# gomasuno.net
KiCad netlist of a schematic drawn in EAGLE
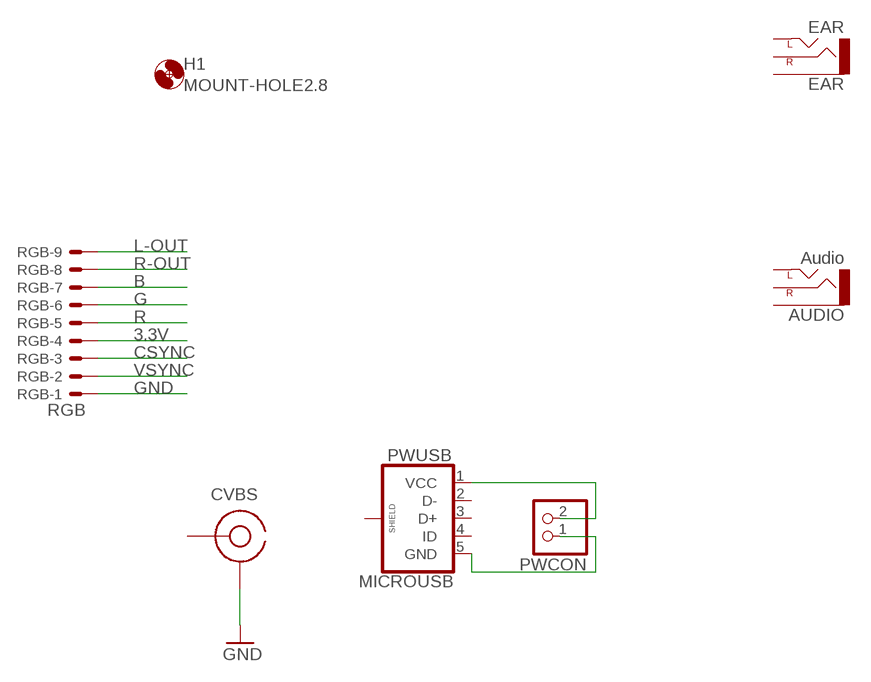
[diagram p0: schematic, sheet 1]

(export (version "E")
  (design (tool "Eeschema 10.0.6"))
  (components
    (comp (ref "AUDIO")
      (value "Audio")
      (footprint "eagle-import:AUDIO-JACK")
      (libsource (lib "eagle-import") (part "AUDIO-JACKPTH"))
    )
    (comp (ref "CVBS")
      (value "RCA")
      (footprint "eagle-import:RCA")
      (libsource (lib "eagle-import") (part "RCA"))
    )
    (comp (ref "EAR")
      (value "EAR")
      (footprint "eagle-import:AUDIO-JACK")
      (libsource (lib "eagle-import") (part "AUDIO-JACKPTH"))
    )
    (comp (ref "H1")
      (value "MOUNT-HOLE2.8")
      (footprint "eagle-import:2,8")
      (libsource (lib "eagle-import") (part "MOUNT-HOLE2.8"))
    )
    (comp (ref "PWCON")
      (value "PINHD-1X2")
      (footprint "eagle-import:1X02")
      (libsource (lib "eagle-import") (part "PINHD-1X2"))
    )
    (comp (ref "PWUSB")
      (value "MICROUSB")
      (footprint "eagle-import:MICRO_USB_1PRIMARY")
      (libsource (lib "eagle-import") (part "MICROUSB"))
    )
    (comp (ref "RGB")
      (value "RGB")
      (footprint "eagle-import:53048-09")
      (fields (field (name "MPN") "53048-0910"))
      (libsource (lib "eagle-import") (part "53?-09048"))
    )
  )
  (nets
    (net (code "1") (name "/3.3V") (class "Default")
      (node (ref "RGB") (pin "4") (pinfunction "S_4") (pintype "passive"))
    )
    (net (code "2") (name "/B") (class "Default")
      (node (ref "RGB") (pin "7") (pinfunction "S_7") (pintype "passive"))
    )
    (net (code "3") (name "/CSYNC") (class "Default")
      (node (ref "RGB") (pin "3") (pinfunction "S_3") (pintype "passive"))
    )
    (net (code "4") (name "/G") (class "Default")
      (node (ref "RGB") (pin "6") (pinfunction "S_6") (pintype "passive"))
    )
    (net (code "5") (name "/L-OUT") (class "Default")
      (node (ref "RGB") (pin "9") (pinfunction "S_9") (pintype "passive"))
    )
    (net (code "6") (name "/R") (class "Default")
      (node (ref "RGB") (pin "5") (pinfunction "S_5") (pintype "passive"))
    )
    (net (code "7") (name "/R-OUT") (class "Default")
      (node (ref "RGB") (pin "8") (pinfunction "S_8") (pintype "passive"))
    )
    (net (code "8") (name "/VSYNC") (class "Default")
      (node (ref "RGB") (pin "2") (pinfunction "S_2") (pintype "passive"))
    )
    (net (code "9") (name "GND") (class "Default")
      (node (ref "CVBS") (pin "GND") (pinfunction "GND_GND") (pintype "passive"))
      (node (ref "PWCON") (pin "1") (pinfunction "1_1") (pintype "passive"))
      (node (ref "PWUSB") (pin "5") (pinfunction "GND_5") (pintype "bidirectional"))
      (node (ref "RGB") (pin "1") (pinfunction "S_1") (pintype "passive"))
    )
    (net (code "10") (name "Net-(PWUSB-VCC)") (class "Default")
      (node (ref "PWCON") (pin "2") (pinfunction "2_2") (pintype "passive"))
      (node (ref "PWUSB") (pin "1") (pinfunction "VCC_1") (pintype "bidirectional"))
    )
    (net (code "11") (name "unconnected-(AUDIO-LEFT-PadTIP)") (class "Default")
      (node (ref "AUDIO") (pin "TIP") (pinfunction "LEFT_TIP") (pintype "bidirectional"))
    )
    (net (code "12") (name "unconnected-(AUDIO-PadSLEEVE)") (class "Default")
      (node (ref "AUDIO") (pin "SLEEVE") (pinfunction "SLEEVE_SLEEVE") (pintype "bidirectional"))
    )
    (net (code "13") (name "unconnected-(AUDIO-RIGHT-PadRING)") (class "Default")
      (node (ref "AUDIO") (pin "RING") (pinfunction "RIGHT_RING") (pintype "bidirectional"))
    )
    (net (code "14") (name "unconnected-(CVBS-PadSIG)") (class "Default")
      (node (ref "CVBS") (pin "SIG") (pinfunction "SIG_SIG") (pintype "passive"))
    )
    (net (code "15") (name "unconnected-(EAR-LEFT-PadTIP)") (class "Default")
      (node (ref "EAR") (pin "TIP") (pinfunction "LEFT_TIP") (pintype "bidirectional"))
    )
    (net (code "16") (name "unconnected-(EAR-PadSLEEVE)") (class "Default")
      (node (ref "EAR") (pin "SLEEVE") (pinfunction "SLEEVE_SLEEVE") (pintype "bidirectional"))
    )
    (net (code "17") (name "unconnected-(EAR-RIGHT-PadRING)") (class "Default")
      (node (ref "EAR") (pin "RING") (pinfunction "RIGHT_RING") (pintype "bidirectional"))
    )
    (net (code "18") (name "unconnected-(PWUSB-D+-Pad3)") (class "Default")
      (node (ref "PWUSB") (pin "3") (pinfunction "D+_3") (pintype "bidirectional"))
    )
    (net (code "19") (name "unconnected-(PWUSB-D--Pad2)") (class "Default")
      (node (ref "PWUSB") (pin "2") (pinfunction "D-_2") (pintype "bidirectional"))
    )
    (net (code "20") (name "unconnected-(PWUSB-ID-Pad4)") (class "Default")
      (node (ref "PWUSB") (pin "4") (pinfunction "ID_4") (pintype "bidirectional"))
    )
    (net (code "21") (name "unconnected-(PWUSB-SHIELD-Pad6)") (class "Default")
      (node (ref "PWUSB") (pin "6") (pinfunction "SHIELD_6") (pintype "bidirectional"))
    )
  )
)
